# MainBoard_V1_3.net
KiCad netlist of a schematic drawn in EAGLE
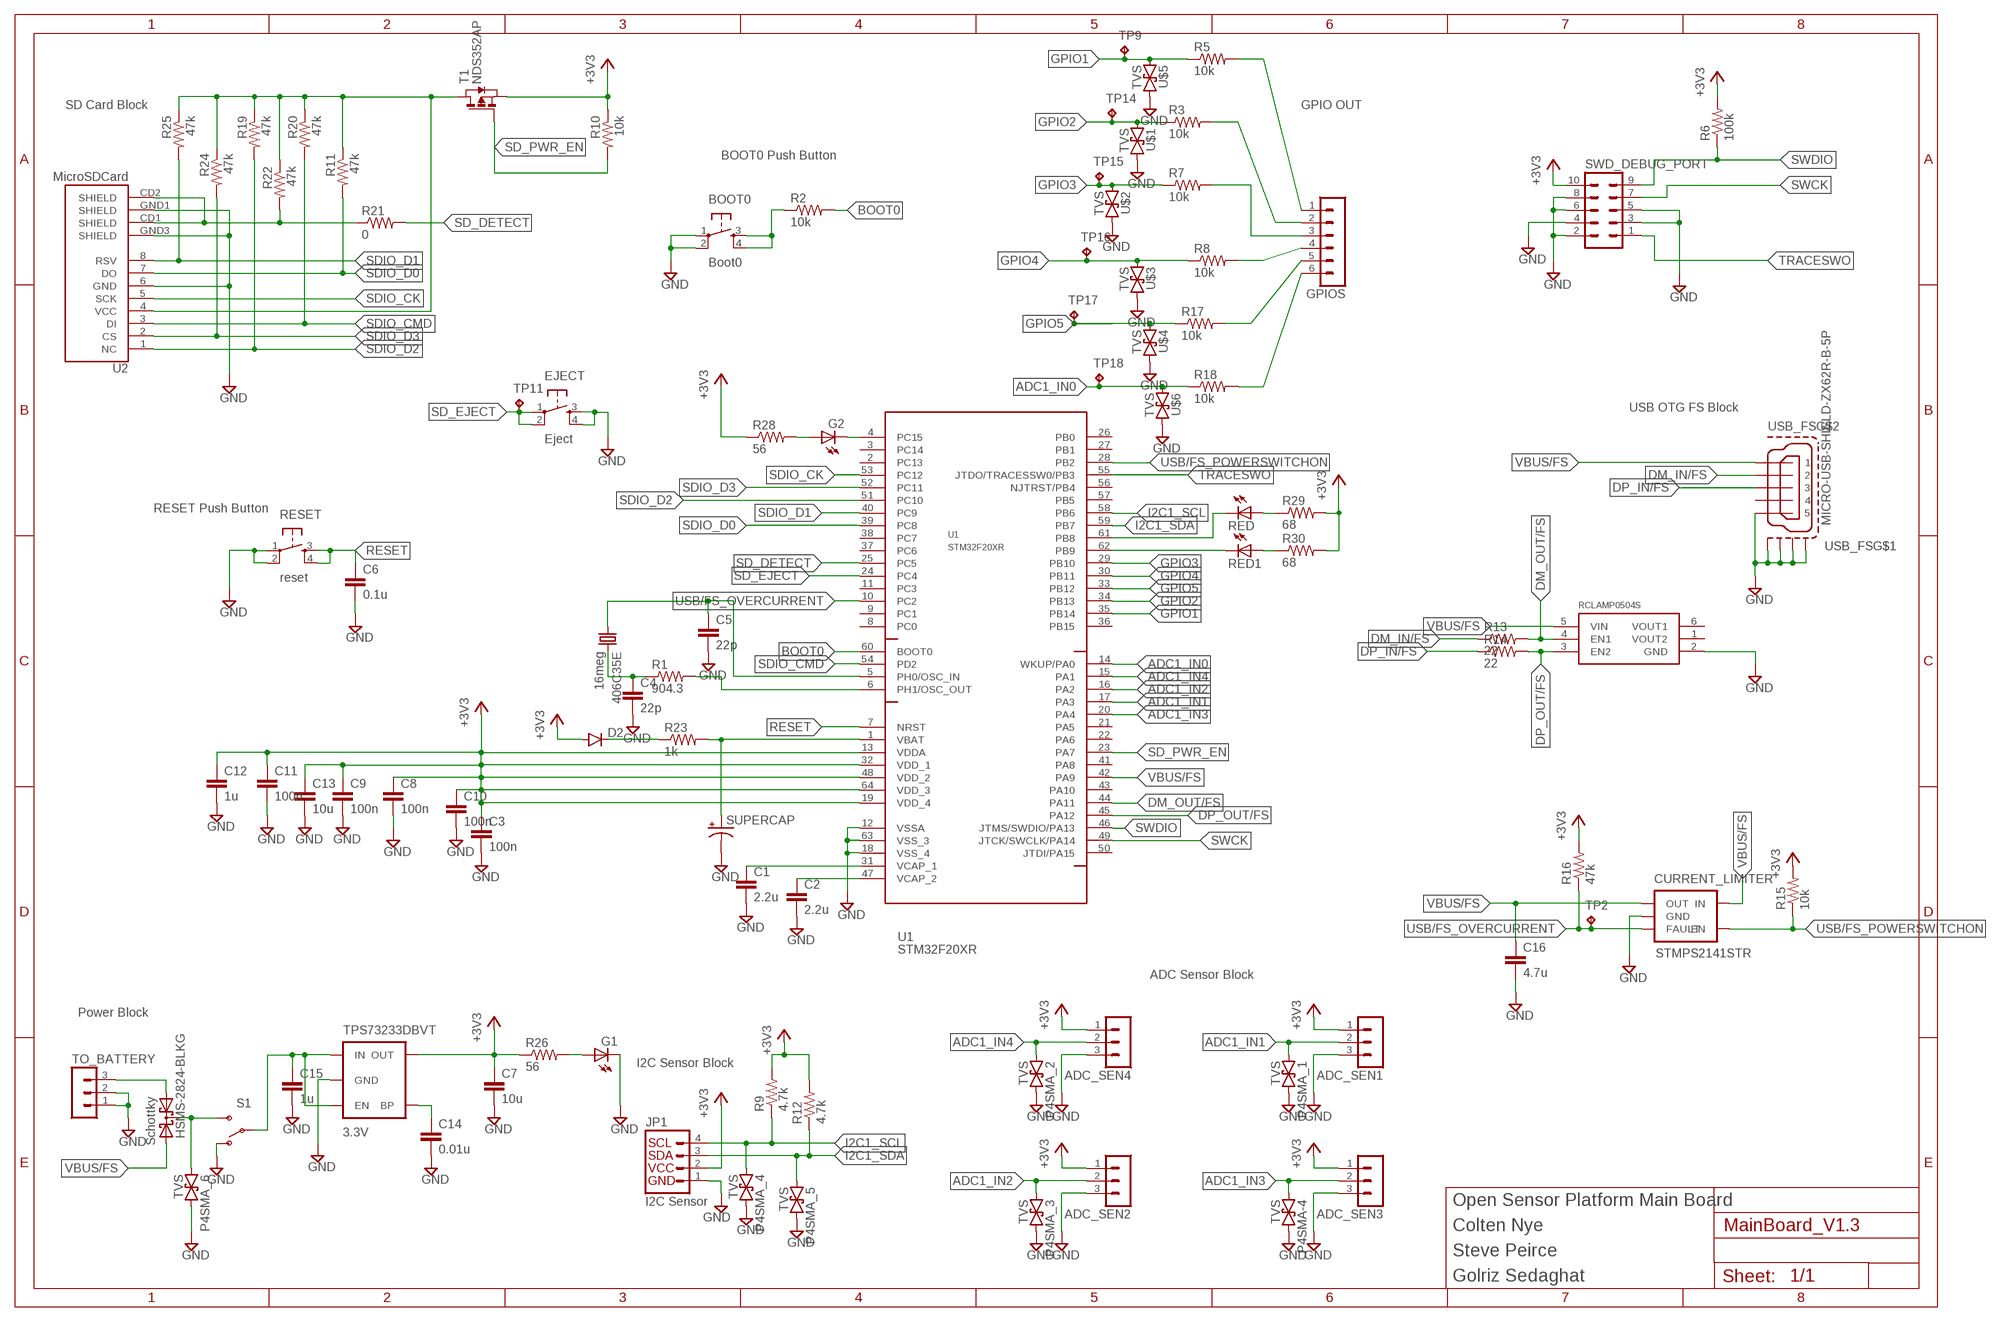
[diagram p0: schematic, sheet 1]

(export (version "E")
  (design (tool "Eeschema 10.0.6"))
  (components
    (comp (ref "406C35E")
      (value "16meg")
      (footprint "eagle-import:CTS406")
      (libsource (lib "eagle-import") (part "CRYSTALCTS406"))
    )
    (comp (ref "ADC_SEN1")
      (value "MA03-1")
      (footprint "eagle-import:MA03-1")
      (libsource (lib "eagle-import") (part "MA03-1"))
    )
    (comp (ref "ADC_SEN2")
      (value "MA03-1")
      (footprint "eagle-import:MA03-1")
      (libsource (lib "eagle-import") (part "MA03-1"))
    )
    (comp (ref "ADC_SEN3")
      (value "MA03-1")
      (footprint "eagle-import:MA03-1")
      (libsource (lib "eagle-import") (part "MA03-1"))
    )
    (comp (ref "ADC_SEN4")
      (value "MA03-1")
      (footprint "eagle-import:MA03-1")
      (libsource (lib "eagle-import") (part "MA03-1"))
    )
    (comp (ref "BOOT0")
      (value "Boot0")
      (footprint "eagle-import:TACTILE-SWITCH-SMD")
      (libsource (lib "eagle-import") (part "TAC_SWITCHSMD"))
    )
    (comp (ref "C1")
      (value "2.2u")
      (footprint "eagle-import:C0805")
      (libsource (lib "eagle-import") (part "C-EUC0805"))
    )
    (comp (ref "C2")
      (value "2.2u")
      (footprint "eagle-import:C0805")
      (libsource (lib "eagle-import") (part "C-EUC0805"))
    )
    (comp (ref "C3")
      (value "100n")
      (footprint "eagle-import:C0805")
      (libsource (lib "eagle-import") (part "C-EUC0805"))
    )
    (comp (ref "C4")
      (value "22p")
      (footprint "eagle-import:C0805")
      (libsource (lib "eagle-import") (part "C-EUC0805"))
    )
    (comp (ref "C5")
      (value "22p")
      (footprint "eagle-import:C0805")
      (libsource (lib "eagle-import") (part "C-EUC0805"))
    )
    (comp (ref "C6")
      (value "0.1u")
      (footprint "eagle-import:C0805")
      (libsource (lib "eagle-import") (part "C-EUC0805"))
    )
    (comp (ref "C7")
      (value "10u")
      (footprint "eagle-import:C0805")
      (libsource (lib "eagle-import") (part "C-EUC0805"))
    )
    (comp (ref "C8")
      (value "100n")
      (footprint "eagle-import:C0805")
      (libsource (lib "eagle-import") (part "C-EUC0805"))
    )
    (comp (ref "C9")
      (value "100n")
      (footprint "eagle-import:C0805")
      (libsource (lib "eagle-import") (part "C-EUC0805"))
    )
    (comp (ref "C10")
      (value "100n")
      (footprint "eagle-import:C0805")
      (libsource (lib "eagle-import") (part "C-EUC0805"))
    )
    (comp (ref "C11")
      (value "100n")
      (footprint "eagle-import:C0805")
      (libsource (lib "eagle-import") (part "C-EUC0805"))
    )
    (comp (ref "C12")
      (value "1u")
      (footprint "eagle-import:C0805")
      (libsource (lib "eagle-import") (part "C-EUC0805"))
    )
    (comp (ref "C13")
      (value "10u")
      (footprint "eagle-import:C0805")
      (libsource (lib "eagle-import") (part "C-EUC0805"))
    )
    (comp (ref "C14")
      (value "0.01u")
      (footprint "eagle-import:C0805")
      (libsource (lib "eagle-import") (part "C-EUC0805"))
    )
    (comp (ref "C15")
      (value "1u")
      (footprint "eagle-import:C0805")
      (libsource (lib "eagle-import") (part "C-EUC0805"))
    )
    (comp (ref "C16")
      (value "4.7u")
      (footprint "eagle-import:C0805")
      (libsource (lib "eagle-import") (part "C-EUC0805"))
    )
    (comp (ref "CURRENT_LIMITER")
      (value "STMPS2141STR")
      (footprint "eagle-import:SOT23-5")
      (libsource (lib "eagle-import") (part "V_REG_NCP1400SOT23-5"))
    )
    (comp (ref "D2")
      (value "DIODESMA")
      (footprint "eagle-import:SMA-DIODE")
      (libsource (lib "eagle-import") (part "DIODESMA"))
    )
    (comp (ref "EJECT")
      (value "Eject")
      (footprint "eagle-import:TACTILE-SWITCH-SMD")
      (libsource (lib "eagle-import") (part "TAC_SWITCHSMD"))
    )
    (comp (ref "G1")
      (value "LEDSML0805")
      (footprint "eagle-import:SML0805")
      (libsource (lib "eagle-import") (part "LEDSML0805"))
    )
    (comp (ref "G2")
      (value "LEDSML0805")
      (footprint "eagle-import:SML0805")
      (libsource (lib "eagle-import") (part "LEDSML0805"))
    )
    (comp (ref "GPIOS")
      (value "MA06-1")
      (footprint "eagle-import:MA06-1")
      (libsource (lib "eagle-import") (part "MA06-1"))
    )
    (comp (ref "HSMS-2824-BLKG")
      (value "Schottky")
      (footprint "eagle-import:SOT23")
      (libsource (lib "eagle-import") (part "BAS70-05"))
    )
    (comp (ref "JP1")
      (value "I2C Sensor")
      (footprint "eagle-import:1X04")
      (libsource (lib "eagle-import") (part "I2C_STANDARD"))
    )
    (comp (ref "P4SMA-4")
      (value "TVS")
      (footprint "eagle-import:SMA-DIODE")
      (libsource (lib "eagle-import") (part "TVS"))
    )
    (comp (ref "P4SMA_1")
      (value "TVS")
      (footprint "eagle-import:SMA-DIODE")
      (libsource (lib "eagle-import") (part "TVS"))
    )
    (comp (ref "P4SMA_2")
      (value "TVS")
      (footprint "eagle-import:SMA-DIODE")
      (libsource (lib "eagle-import") (part "TVS"))
    )
    (comp (ref "P4SMA_3")
      (value "TVS")
      (footprint "eagle-import:SMA-DIODE")
      (libsource (lib "eagle-import") (part "TVS"))
    )
    (comp (ref "P4SMA_4")
      (value "TVS")
      (footprint "eagle-import:SMA-DIODE")
      (libsource (lib "eagle-import") (part "TVS"))
    )
    (comp (ref "P4SMA_5")
      (value "TVS")
      (footprint "eagle-import:SMA-DIODE")
      (libsource (lib "eagle-import") (part "TVS"))
    )
    (comp (ref "P4SMA_6")
      (value "TVS")
      (footprint "eagle-import:SMA-DIODE")
      (libsource (lib "eagle-import") (part "TVS"))
    )
    (comp (ref "R1")
      (value "904.3")
      (footprint "eagle-import:R0805")
      (libsource (lib "eagle-import") (part "R-US_R0805"))
    )
    (comp (ref "R2")
      (value "10k")
      (footprint "eagle-import:R0805")
      (libsource (lib "eagle-import") (part "R-US_R0805"))
    )
    (comp (ref "R3")
      (value "10k")
      (footprint "eagle-import:R0805")
      (libsource (lib "eagle-import") (part "R-US_R0805"))
    )
    (comp (ref "R5")
      (value "10k")
      (footprint "eagle-import:R0805")
      (libsource (lib "eagle-import") (part "R-US_R0805"))
    )
    (comp (ref "R6")
      (value "100k")
      (footprint "eagle-import:R0805")
      (libsource (lib "eagle-import") (part "R-US_R0805"))
    )
    (comp (ref "R7")
      (value "10k")
      (footprint "eagle-import:R0805")
      (libsource (lib "eagle-import") (part "R-US_R0805"))
    )
    (comp (ref "R8")
      (value "10k")
      (footprint "eagle-import:R0805")
      (libsource (lib "eagle-import") (part "R-US_R0805"))
    )
    (comp (ref "R9")
      (value "4.7k")
      (footprint "eagle-import:R0805")
      (libsource (lib "eagle-import") (part "R-US_R0805"))
    )
    (comp (ref "R10")
      (value "10k")
      (footprint "eagle-import:R0805")
      (libsource (lib "eagle-import") (part "R-US_R0805"))
    )
    (comp (ref "R11")
      (value "47k")
      (footprint "eagle-import:R0805")
      (libsource (lib "eagle-import") (part "R-US_R0805"))
    )
    (comp (ref "R12")
      (value "4.7k")
      (footprint "eagle-import:R0805")
      (libsource (lib "eagle-import") (part "R-US_R0805"))
    )
    (comp (ref "R13")
      (value "22")
      (footprint "eagle-import:R0805")
      (libsource (lib "eagle-import") (part "R-US_R0805"))
    )
    (comp (ref "R14")
      (value "22")
      (footprint "eagle-import:R0805")
      (libsource (lib "eagle-import") (part "R-US_R0805"))
    )
    (comp (ref "R15")
      (value "10k")
      (footprint "eagle-import:R0805")
      (libsource (lib "eagle-import") (part "R-US_R0805"))
    )
    (comp (ref "R16")
      (value "47k")
      (footprint "eagle-import:R0805")
      (libsource (lib "eagle-import") (part "R-US_R0805"))
    )
    (comp (ref "R17")
      (value "10k")
      (footprint "eagle-import:R0805")
      (libsource (lib "eagle-import") (part "R-US_R0805"))
    )
    (comp (ref "R18")
      (value "10k")
      (footprint "eagle-import:R0805")
      (libsource (lib "eagle-import") (part "R-US_R0805"))
    )
    (comp (ref "R19")
      (value "47k")
      (footprint "eagle-import:R0805")
      (libsource (lib "eagle-import") (part "R-US_R0805"))
    )
    (comp (ref "R20")
      (value "47k")
      (footprint "eagle-import:R0805")
      (libsource (lib "eagle-import") (part "R-US_R0805"))
    )
    (comp (ref "R21")
      (value "0")
      (footprint "eagle-import:R0805")
      (libsource (lib "eagle-import") (part "R-US_R0805"))
    )
    (comp (ref "R22")
      (value "47k")
      (footprint "eagle-import:R0805")
      (libsource (lib "eagle-import") (part "R-US_R0805"))
    )
    (comp (ref "R23")
      (value "1k")
      (footprint "eagle-import:R0805")
      (libsource (lib "eagle-import") (part "R-US_R0805"))
    )
    (comp (ref "R24")
      (value "47k")
      (footprint "eagle-import:R0805")
      (libsource (lib "eagle-import") (part "R-US_R0805"))
    )
    (comp (ref "R25")
      (value "47k")
      (footprint "eagle-import:R0805")
      (libsource (lib "eagle-import") (part "R-US_R0805"))
    )
    (comp (ref "R26")
      (value "56")
      (footprint "eagle-import:R0805")
      (libsource (lib "eagle-import") (part "R-US_R0805"))
    )
    (comp (ref "R28")
      (value "56")
      (footprint "eagle-import:R0805")
      (libsource (lib "eagle-import") (part "R-US_R0805"))
    )
    (comp (ref "R29")
      (value "68")
      (footprint "eagle-import:R0805")
      (libsource (lib "eagle-import") (part "R-US_R0805"))
    )
    (comp (ref "R30")
      (value "68")
      (footprint "eagle-import:R0805")
      (libsource (lib "eagle-import") (part "R-US_R0805"))
    )
    (comp (ref "RCLAMP0504S")
      (value "VREG_SOT23-6_DUALAP7312")
      (footprint "eagle-import:SOT23-6")
      (libsource (lib "eagle-import") (part "VREG_SOT23-6_DUALAP7312"))
    )
    (comp (ref "RED")
      (value "LEDSML0805")
      (footprint "eagle-import:SML0805")
      (libsource (lib "eagle-import") (part "LEDSML0805"))
    )
    (comp (ref "RED1")
      (value "LEDSML0805")
      (footprint "eagle-import:SML0805")
      (libsource (lib "eagle-import") (part "LEDSML0805"))
    )
    (comp (ref "RESET")
      (value "reset")
      (footprint "eagle-import:TACTILE-SWITCH-SMD")
      (libsource (lib "eagle-import") (part "TAC_SWITCHSMD"))
    )
    (comp (ref "S1")
      (value "SWITCH-SPDTSMD")
      (footprint "eagle-import:AYZ0202")
      (libsource (lib "eagle-import") (part "SWITCH-SPDTSMD"))
    )
    (comp (ref "SUPERCAP")
      (value "SUPERCAP")
      (footprint "eagle-import:414-VA5R")
      (libsource (lib "eagle-import") (part "SUPERCAP"))
    )
    (comp (ref "SWD_DEBUG_PORT")
      (value "MA05-2")
      (footprint "eagle-import:MA05-2")
      (libsource (lib "eagle-import") (part "MA05-2"))
    )
    (comp (ref "T1")
      (value "NDS352AP")
      (footprint "eagle-import:SOT-23")
      (libsource (lib "eagle-import") (part "PMOSSOT23"))
    )
    (comp (ref "TO_BATTERY")
      (value "MA03-1")
      (footprint "eagle-import:MA03-1")
      (libsource (lib "eagle-import") (part "MA03-1"))
    )
    (comp (ref "TP2")
      (value "TPB1,27")
      (footprint "eagle-import:B1,27")
      (libsource (lib "eagle-import") (part "TPB1,27"))
    )
    (comp (ref "TP9")
      (value "TPB1,27")
      (footprint "eagle-import:B1,27")
      (libsource (lib "eagle-import") (part "TPB1,27"))
    )
    (comp (ref "TP11")
      (value "TPB1,27")
      (footprint "eagle-import:B1,27")
      (libsource (lib "eagle-import") (part "TPB1,27"))
    )
    (comp (ref "TP14")
      (value "TPB1,27")
      (footprint "eagle-import:B1,27")
      (libsource (lib "eagle-import") (part "TPB1,27"))
    )
    (comp (ref "TP15")
      (value "TPB1,27")
      (footprint "eagle-import:B1,27")
      (libsource (lib "eagle-import") (part "TPB1,27"))
    )
    (comp (ref "TP16")
      (value "TPB1,27")
      (footprint "eagle-import:B1,27")
      (libsource (lib "eagle-import") (part "TPB1,27"))
    )
    (comp (ref "TP17")
      (value "TPB1,27")
      (footprint "eagle-import:B1,27")
      (libsource (lib "eagle-import") (part "TPB1,27"))
    )
    (comp (ref "TP18")
      (value "TPB1,27")
      (footprint "eagle-import:B1,27")
      (libsource (lib "eagle-import") (part "TPB1,27"))
    )
    (comp (ref "TPS73233DBVT")
      (value "3.3V")
      (footprint "eagle-import:SOT23-5")
      (libsource (lib "eagle-import") (part "V_REG_MIC52053.3V"))
    )
    (comp (ref "U$1")
      (value "TVS")
      (footprint "eagle-import:SMA-DIODE")
      (libsource (lib "eagle-import") (part "TVS"))
    )
    (comp (ref "U$2")
      (value "TVS")
      (footprint "eagle-import:SMA-DIODE")
      (libsource (lib "eagle-import") (part "TVS"))
    )
    (comp (ref "U$3")
      (value "TVS")
      (footprint "eagle-import:SMA-DIODE")
      (libsource (lib "eagle-import") (part "TVS"))
    )
    (comp (ref "U$4")
      (value "TVS")
      (footprint "eagle-import:SMA-DIODE")
      (libsource (lib "eagle-import") (part "TVS"))
    )
    (comp (ref "U$5")
      (value "TVS")
      (footprint "eagle-import:SMA-DIODE")
      (libsource (lib "eagle-import") (part "TVS"))
    )
    (comp (ref "U$6")
      (value "TVS")
      (footprint "eagle-import:SMA-DIODE")
      (libsource (lib "eagle-import") (part "TVS"))
    )
    (comp (ref "U1")
      (value "STM32F20XR")
      (footprint "eagle-import:LQFP64")
      (libsource (lib "eagle-import") (part "STM32F20XR"))
    )
    (comp (ref "U2")
      (value "MicroSDCard")
      (footprint "eagle-import:MICRO-SD-SOCKET-PP")
      (libsource (lib "eagle-import") (part "USD-SOCKETNEW"))
    )
    (comp (ref "USB_FS")
      (value "MICRO-USB-SHIELD-ZX62R-B-5P")
      (footprint "eagle-import:ZX62R-B-5P")
      (libsource (lib "eagle-import") (part "MICRO-USB-SHIELD-ZX62R-B-5P"))
    )
  )
  (nets
    (net (code "1") (name "+3V3") (class "Default")
      (node (ref "ADC_SEN1") (pin "1") (pinfunction "1_1") (pintype "passive"))
      (node (ref "ADC_SEN2") (pin "1") (pinfunction "1_1") (pintype "passive"))
      (node (ref "ADC_SEN3") (pin "1") (pinfunction "1_1") (pintype "passive"))
      (node (ref "ADC_SEN4") (pin "1") (pinfunction "1_1") (pintype "passive"))
      (node (ref "C10") (pin "1") (pinfunction "1_1") (pintype "passive"))
      (node (ref "C11") (pin "1") (pinfunction "1_1") (pintype "passive"))
      (node (ref "C12") (pin "1") (pinfunction "1_1") (pintype "passive"))
      (node (ref "C13") (pin "1") (pinfunction "1_1") (pintype "passive"))
      (node (ref "C3") (pin "1") (pinfunction "1_1") (pintype "passive"))
      (node (ref "C7") (pin "1") (pinfunction "1_1") (pintype "passive"))
      (node (ref "C8") (pin "1") (pinfunction "1_1") (pintype "passive"))
      (node (ref "C9") (pin "1") (pinfunction "1_1") (pintype "passive"))
      (node (ref "D2") (pin "A") (pinfunction "A_A") (pintype "passive"))
      (node (ref "JP1") (pin "2") (pinfunction "2_2") (pintype "passive"))
      (node (ref "R10") (pin "1") (pinfunction "1_1") (pintype "passive"))
      (node (ref "R12") (pin "2") (pinfunction "2_2") (pintype "passive"))
      (node (ref "R15") (pin "2") (pinfunction "2_2") (pintype "passive"))
      (node (ref "R16") (pin "2") (pinfunction "2_2") (pintype "passive"))
      (node (ref "R26") (pin "1") (pinfunction "1_1") (pintype "passive"))
      (node (ref "R28") (pin "1") (pinfunction "1_1") (pintype "passive"))
      (node (ref "R29") (pin "2") (pinfunction "2_2") (pintype "passive"))
      (node (ref "R30") (pin "2") (pinfunction "2_2") (pintype "passive"))
      (node (ref "R6") (pin "2") (pinfunction "2_2") (pintype "passive"))
      (node (ref "R9") (pin "2") (pinfunction "2_2") (pintype "passive"))
      (node (ref "SWD_DEBUG_PORT") (pin "10") (pinfunction "10_10") (pintype "passive"))
      (node (ref "T1") (pin "2") (pinfunction "S_2") (pintype "passive"))
      (node (ref "TPS73233DBVT") (pin "5") (pinfunction "OUT_5") (pintype "passive"))
      (node (ref "U1") (pin "13") (pinfunction "VDDA_13") (pintype "power_in"))
      (node (ref "U1") (pin "19") (pinfunction "VDD_4_19") (pintype "power_in"))
      (node (ref "U1") (pin "32") (pinfunction "VDD_1_32") (pintype "power_in"))
      (node (ref "U1") (pin "48") (pinfunction "VDD_2_48") (pintype "power_in"))
      (node (ref "U1") (pin "64") (pinfunction "VDD_3_64") (pintype "power_in"))
    )
    (net (code "2") (name "ADC1_IN0") (class "Default")
      (node (ref "R18") (pin "1") (pinfunction "1_1") (pintype "passive"))
      (node (ref "TP18") (pin "TP") (pinfunction "TP_TP") (pintype "input"))
      (node (ref "U$6") (pin "A") (pinfunction "1_A") (pintype "passive"))
      (node (ref "U1") (pin "14") (pinfunction "WKUP/PA0_14") (pintype "bidirectional"))
    )
    (net (code "3") (name "ADC1_IN1") (class "Default")
      (node (ref "ADC_SEN1") (pin "2") (pinfunction "2_2") (pintype "passive"))
      (node (ref "P4SMA_1") (pin "A") (pinfunction "1_A") (pintype "passive"))
      (node (ref "U1") (pin "17") (pinfunction "PA3_17") (pintype "bidirectional"))
    )
    (net (code "4") (name "ADC1_IN2") (class "Default")
      (node (ref "ADC_SEN2") (pin "2") (pinfunction "2_2") (pintype "passive"))
      (node (ref "P4SMA_3") (pin "A") (pinfunction "1_A") (pintype "passive"))
      (node (ref "U1") (pin "16") (pinfunction "PA2_16") (pintype "bidirectional"))
    )
    (net (code "5") (name "ADC1_IN3") (class "Default")
      (node (ref "ADC_SEN3") (pin "2") (pinfunction "2_2") (pintype "passive"))
      (node (ref "P4SMA-4") (pin "A") (pinfunction "1_A") (pintype "passive"))
      (node (ref "U1") (pin "20") (pinfunction "PA4_20") (pintype "bidirectional"))
    )
    (net (code "6") (name "ADC1_IN4") (class "Default")
      (node (ref "ADC_SEN4") (pin "2") (pinfunction "2_2") (pintype "passive"))
      (node (ref "P4SMA_2") (pin "A") (pinfunction "1_A") (pintype "passive"))
      (node (ref "U1") (pin "15") (pinfunction "PA1_15") (pintype "bidirectional"))
    )
    (net (code "7") (name "BOOT0") (class "Default")
      (node (ref "R2") (pin "2") (pinfunction "2_2") (pintype "passive"))
      (node (ref "U1") (pin "60") (pinfunction "BOOT0_60") (pintype "bidirectional"))
    )
    (net (code "8") (name "DM_IN{slash}FS") (class "Default")
      (node (ref "R13") (pin "1") (pinfunction "1_1") (pintype "passive"))
      (node (ref "USB_FS") (pin "2") (pinfunction "2_2") (pintype "input"))
    )
    (net (code "9") (name "DM_OUT{slash}FS") (class "Default")
      (node (ref "R13") (pin "2") (pinfunction "2_2") (pintype "passive"))
      (node (ref "RCLAMP0504S") (pin "4") (pinfunction "EN1_4") (pintype "bidirectional"))
      (node (ref "U1") (pin "44") (pinfunction "PA11_44") (pintype "bidirectional"))
    )
    (net (code "10") (name "DP_IN{slash}FS") (class "Default")
      (node (ref "R14") (pin "1") (pinfunction "1_1") (pintype "passive"))
      (node (ref "USB_FS") (pin "3") (pinfunction "3_3") (pintype "input"))
    )
    (net (code "11") (name "DP_OUT{slash}FS") (class "Default")
      (node (ref "R14") (pin "2") (pinfunction "2_2") (pintype "passive"))
      (node (ref "RCLAMP0504S") (pin "3") (pinfunction "EN2_3") (pintype "bidirectional"))
      (node (ref "U1") (pin "45") (pinfunction "PA12_45") (pintype "bidirectional"))
    )
    (net (code "12") (name "GND") (class "Default")
      (node (ref "ADC_SEN1") (pin "3") (pinfunction "3_3") (pintype "passive"))
      (node (ref "ADC_SEN2") (pin "3") (pinfunction "3_3") (pintype "passive"))
      (node (ref "ADC_SEN3") (pin "3") (pinfunction "3_3") (pintype "passive"))
      (node (ref "ADC_SEN4") (pin "3") (pinfunction "3_3") (pintype "passive"))
      (node (ref "BOOT0") (pin "1") (pinfunction "1_1") (pintype "passive"))
      (node (ref "BOOT0") (pin "2") (pinfunction "2_2") (pintype "passive"))
      (node (ref "C1") (pin "2") (pinfunction "2_2") (pintype "passive"))
      (node (ref "C10") (pin "2") (pinfunction "2_2") (pintype "passive"))
      (node (ref "C11") (pin "2") (pinfunction "2_2") (pintype "passive"))
      (node (ref "C12") (pin "2") (pinfunction "2_2") (pintype "passive"))
      (node (ref "C13") (pin "2") (pinfunction "2_2") (pintype "passive"))
      (node (ref "C14") (pin "2") (pinfunction "2_2") (pintype "passive"))
      (node (ref "C15") (pin "2") (pinfunction "2_2") (pintype "passive"))
      (node (ref "C16") (pin "2") (pinfunction "2_2") (pintype "passive"))
      (node (ref "C2") (pin "2") (pinfunction "2_2") (pintype "passive"))
      (node (ref "C3") (pin "2") (pinfunction "2_2") (pintype "passive"))
      (node (ref "C4") (pin "2") (pinfunction "2_2") (pintype "passive"))
      (node (ref "C5") (pin "2") (pinfunction "2_2") (pintype "passive"))
      (node (ref "C6") (pin "2") (pinfunction "2_2") (pintype "passive"))
      (node (ref "C7") (pin "2") (pinfunction "2_2") (pintype "passive"))
      (node (ref "C8") (pin "2") (pinfunction "2_2") (pintype "passive"))
      (node (ref "C9") (pin "2") (pinfunction "2_2") (pintype "passive"))
      (node (ref "CURRENT_LIMITER") (pin "4") (pinfunction "GND_4") (pintype "input"))
      (node (ref "EJECT") (pin "3") (pinfunction "3_3") (pintype "passive"))
      (node (ref "EJECT") (pin "4") (pinfunction "4_4") (pintype "passive"))
      (node (ref "G1") (pin "C") (pinfunction "C_C") (pintype "passive"))
      (node (ref "JP1") (pin "1") (pinfunction "1_1") (pintype "passive"))
      (node (ref "P4SMA-4") (pin "C") (pinfunction "2_C") (pintype "passive"))
      (node (ref "P4SMA_1") (pin "C") (pinfunction "2_C") (pintype "passive"))
      (node (ref "P4SMA_2") (pin "C") (pinfunction "2_C") (pintype "passive"))
      (node (ref "P4SMA_3") (pin "C") (pinfunction "2_C") (pintype "passive"))
      (node (ref "P4SMA_4") (pin "C") (pinfunction "2_C") (pintype "passive"))
      (node (ref "P4SMA_5") (pin "C") (pinfunction "2_C") (pintype "passive"))
      (node (ref "P4SMA_6") (pin "C") (pinfunction "2_C") (pintype "passive"))
      (node (ref "RCLAMP0504S") (pin "2") (pinfunction "GND_2") (pintype "bidirectional"))
      (node (ref "RESET") (pin "1") (pinfunction "1_1") (pintype "passive"))
      (node (ref "RESET") (pin "2") (pinfunction "2_2") (pintype "passive"))
      (node (ref "S1") (pin "1") (pinfunction "O_1") (pintype "passive"))
      (node (ref "SUPERCAP") (pin "-") (pinfunction "-_-") (pintype "passive"))
      (node (ref "SWD_DEBUG_PORT") (pin "2") (pinfunction "2_2") (pintype "passive"))
      (node (ref "SWD_DEBUG_PORT") (pin "3") (pinfunction "3_3") (pintype "passive"))
      (node (ref "SWD_DEBUG_PORT") (pin "4") (pinfunction "4_4") (pintype "passive"))
      (node (ref "SWD_DEBUG_PORT") (pin "5") (pinfunction "5_5") (pintype "passive"))
      (node (ref "SWD_DEBUG_PORT") (pin "6") (pinfunction "6_6") (pintype "passive"))
      (node (ref "SWD_DEBUG_PORT") (pin "8") (pinfunction "8_8") (pintype "passive"))
      (node (ref "TO_BATTERY") (pin "1") (pinfunction "1_1") (pintype "passive"))
      (node (ref "TO_BATTERY") (pin "2") (pinfunction "2_2") (pintype "passive"))
      (node (ref "TPS73233DBVT") (pin "2") (pinfunction "GND_2") (pintype "input"))
      (node (ref "U$1") (pin "C") (pinfunction "2_C") (pintype "passive"))
      (node (ref "U$2") (pin "C") (pinfunction "2_C") (pintype "passive"))
      (node (ref "U$3") (pin "C") (pinfunction "2_C") (pintype "passive"))
      (node (ref "U$4") (pin "C") (pinfunction "2_C") (pintype "passive"))
      (node (ref "U$5") (pin "C") (pinfunction "2_C") (pintype "passive"))
      (node (ref "U$6") (pin "C") (pinfunction "2_C") (pintype "passive"))
      (node (ref "U1") (pin "12") (pinfunction "VSSA_12") (pintype "power_in"))
      (node (ref "U1") (pin "18") (pinfunction "VSS_4_18") (pintype "power_in"))
      (node (ref "U1") (pin "63") (pinfunction "VSS_3_63") (pintype "power_in"))
      (node (ref "U2") (pin "6") (pinfunction "GND_6") (pintype "bidirectional"))
      (node (ref "U2") (pin "GND1") (pinfunction "SHIELD_GND1") (pintype "bidirectional"))
      (node (ref "U2") (pin "GND3") (pinfunction "SHIELD_GND3") (pintype "bidirectional"))
      (node (ref "USB_FS") (pin "5") (pinfunction "5_5") (pintype "input"))
      (node (ref "USB_FS") (pin "M1") (pinfunction "S1_M1") (pintype "passive"))
      (node (ref "USB_FS") (pin "M2") (pinfunction "S2_M2") (pintype "passive"))
      (node (ref "USB_FS") (pin "M3") (pinfunction "S3_M3") (pintype "passive"))
      (node (ref "USB_FS") (pin "M4") (pinfunction "S4_M4") (pintype "passive"))
    )
    (net (code "13") (name "GPIO1") (class "Default")
      (node (ref "R5") (pin "1") (pinfunction "1_1") (pintype "passive"))
      (node (ref "TP9") (pin "TP") (pinfunction "TP_TP") (pintype "input"))
      (node (ref "U$5") (pin "A") (pinfunction "1_A") (pintype "passive"))
      (node (ref "U1") (pin "35") (pinfunction "PB14_35") (pintype "bidirectional"))
    )
    (net (code "14") (name "GPIO2") (class "Default")
      (node (ref "R3") (pin "1") (pinfunction "1_1") (pintype "passive"))
      (node (ref "TP14") (pin "TP") (pinfunction "TP_TP") (pintype "input"))
      (node (ref "U$1") (pin "A") (pinfunction "1_A") (pintype "passive"))
      (node (ref "U1") (pin "34") (pinfunction "PB13_34") (pintype "bidirectional"))
    )
    (net (code "15") (name "GPIO3") (class "Default")
      (node (ref "R7") (pin "1") (pinfunction "1_1") (pintype "passive"))
      (node (ref "TP15") (pin "TP") (pinfunction "TP_TP") (pintype "input"))
      (node (ref "U$2") (pin "A") (pinfunction "1_A") (pintype "passive"))
      (node (ref "U1") (pin "29") (pinfunction "PB10_29") (pintype "bidirectional"))
    )
    (net (code "16") (name "GPIO4") (class "Default")
      (node (ref "R8") (pin "1") (pinfunction "1_1") (pintype "passive"))
      (node (ref "TP16") (pin "TP") (pinfunction "TP_TP") (pintype "input"))
      (node (ref "U$3") (pin "A") (pinfunction "1_A") (pintype "passive"))
      (node (ref "U1") (pin "30") (pinfunction "PB11_30") (pintype "bidirectional"))
    )
    (net (code "17") (name "GPIO5") (class "Default")
      (node (ref "R17") (pin "1") (pinfunction "1_1") (pintype "passive"))
      (node (ref "TP17") (pin "TP") (pinfunction "TP_TP") (pintype "input"))
      (node (ref "U$4") (pin "A") (pinfunction "1_A") (pintype "passive"))
      (node (ref "U1") (pin "33") (pinfunction "PB12_33") (pintype "bidirectional"))
    )
    (net (code "18") (name "I2C1_SCL") (class "Default")
      (node (ref "JP1") (pin "4") (pinfunction "4_4") (pintype "passive"))
      (node (ref "P4SMA_4") (pin "A") (pinfunction "1_A") (pintype "passive"))
      (node (ref "R9") (pin "1") (pinfunction "1_1") (pintype "passive"))
      (node (ref "U1") (pin "58") (pinfunction "PB6_58") (pintype "bidirectional"))
    )
    (net (code "19") (name "I2C1_SDA") (class "Default")
      (node (ref "JP1") (pin "3") (pinfunction "3_3") (pintype "passive"))
      (node (ref "P4SMA_5") (pin "A") (pinfunction "1_A") (pintype "passive"))
      (node (ref "R12") (pin "1") (pinfunction "1_1") (pintype "passive"))
      (node (ref "U1") (pin "59") (pinfunction "PB7_59") (pintype "bidirectional"))
    )
    (net (code "20") (name "Net-(406C35E-2)") (class "Default")
      (node (ref "406C35E") (pin "3") (pinfunction "2_3") (pintype "passive"))
      (node (ref "C4") (pin "1") (pinfunction "1_1") (pintype "passive"))
      (node (ref "R1") (pin "1") (pinfunction "1_1") (pintype "passive"))
    )
    (net (code "21") (name "Net-(BOOT0-Pad3)") (class "Default")
      (node (ref "BOOT0") (pin "3") (pinfunction "3_3") (pintype "passive"))
      (node (ref "BOOT0") (pin "4") (pinfunction "4_4") (pintype "passive"))
      (node (ref "R2") (pin "1") (pinfunction "1_1") (pintype "passive"))
    )
    (net (code "22") (name "Net-(D2-PadC)") (class "Default")
      (node (ref "D2") (pin "C") (pinfunction "C_C") (pintype "passive"))
      (node (ref "R23") (pin "1") (pinfunction "1_1") (pintype "passive"))
    )
    (net (code "23") (name "Net-(G1-PadA)") (class "Default")
      (node (ref "G1") (pin "A") (pinfunction "A_A") (pintype "passive"))
      (node (ref "R26") (pin "2") (pinfunction "2_2") (pintype "passive"))
    )
    (net (code "24") (name "Net-(G2-PadA)") (class "Default")
      (node (ref "G2") (pin "A") (pinfunction "A_A") (pintype "passive"))
      (node (ref "R28") (pin "2") (pinfunction "2_2") (pintype "passive"))
    )
    (net (code "25") (name "Net-(GPIOS-Pad1)") (class "Default")
      (node (ref "GPIOS") (pin "1") (pinfunction "1_1") (pintype "passive"))
      (node (ref "R5") (pin "2") (pinfunction "2_2") (pintype "passive"))
    )
    (net (code "26") (name "Net-(GPIOS-Pad2)") (class "Default")
      (node (ref "GPIOS") (pin "2") (pinfunction "2_2") (pintype "passive"))
      (node (ref "R3") (pin "2") (pinfunction "2_2") (pintype "passive"))
    )
    (net (code "27") (name "Net-(GPIOS-Pad3)") (class "Default")
      (node (ref "GPIOS") (pin "3") (pinfunction "3_3") (pintype "passive"))
      (node (ref "R7") (pin "2") (pinfunction "2_2") (pintype "passive"))
    )
    (net (code "28") (name "Net-(GPIOS-Pad4)") (class "Default")
      (node (ref "GPIOS") (pin "4") (pinfunction "4_4") (pintype "passive"))
      (node (ref "R8") (pin "2") (pinfunction "2_2") (pintype "passive"))
    )
    (net (code "29") (name "Net-(GPIOS-Pad5)") (class "Default")
      (node (ref "GPIOS") (pin "5") (pinfunction "5_5") (pintype "passive"))
      (node (ref "R17") (pin "2") (pinfunction "2_2") (pintype "passive"))
    )
    (net (code "30") (name "Net-(GPIOS-Pad6)") (class "Default")
      (node (ref "GPIOS") (pin "6") (pinfunction "6_6") (pintype "passive"))
      (node (ref "R18") (pin "2") (pinfunction "2_2") (pintype "passive"))
    )
    (net (code "31") (name "Net-(HSMS-2824-BLKG-A1)") (class "Default")
      (node (ref "HSMS-2824-BLKG") (pin "1") (pinfunction "A1_1") (pintype "passive"))
      (node (ref "TO_BATTERY") (pin "3") (pinfunction "3_3") (pintype "passive"))
    )
    (net (code "32") (name "Net-(HSMS-2824-BLKG-C)") (class "Default")
      (node (ref "HSMS-2824-BLKG") (pin "3") (pinfunction "C_3") (pintype "passive"))
      (node (ref "P4SMA_6") (pin "A") (pinfunction "1_A") (pintype "passive"))
      (node (ref "S1") (pin "3") (pinfunction "S_3") (pintype "passive"))
    )
    (net (code "33") (name "Net-(R21-Pad1)") (class "Default")
      (node (ref "R21") (pin "1") (pinfunction "1_1") (pintype "passive"))
      (node (ref "R22") (pin "2") (pinfunction "2_2") (pintype "passive"))
      (node (ref "U2") (pin "CD1") (pinfunction "SHIELD_CD1") (pintype "bidirectional"))
      (node (ref "U2") (pin "CD2") (pinfunction "SHIELD_CD2") (pintype "bidirectional"))
    )
    (net (code "34") (name "Net-(R29-Pad1)") (class "Default")
      (node (ref "R29") (pin "1") (pinfunction "1_1") (pintype "passive"))
      (node (ref "RED") (pin "A") (pinfunction "A_A") (pintype "passive"))
    )
    (net (code "35") (name "Net-(R30-Pad1)") (class "Default")
      (node (ref "R30") (pin "1") (pinfunction "1_1") (pintype "passive"))
      (node (ref "RED1") (pin "A") (pinfunction "A_A") (pintype "passive"))
    )
    (net (code "36") (name "Net-(S1-P)") (class "Default")
      (node (ref "C15") (pin "1") (pinfunction "1_1") (pintype "passive"))
      (node (ref "S1") (pin "2") (pinfunction "P_2") (pintype "passive"))
      (node (ref "TPS73233DBVT") (pin "1") (pinfunction "IN_1") (pintype "input"))
      (node (ref "TPS73233DBVT") (pin "3") (pinfunction "EN_3") (pintype "input"))
    )
    (net (code "37") (name "Net-(T1-D)") (class "Default")
      (node (ref "R11") (pin "1") (pinfunction "1_1") (pintype "passive"))
      (node (ref "R19") (pin "1") (pinfunction "1_1") (pintype "passive"))
      (node (ref "R20") (pin "1") (pinfunction "1_1") (pintype "passive"))
      (node (ref "R22") (pin "1") (pinfunction "1_1") (pintype "passive"))
      (node (ref "R24") (pin "1") (pinfunction "1_1") (pintype "passive"))
      (node (ref "R25") (pin "1") (pinfunction "1_1") (pintype "passive"))
      (node (ref "T1") (pin "1") (pinfunction "D_1") (pintype "passive"))
      (node (ref "U2") (pin "4") (pinfunction "VCC_4") (pintype "bidirectional"))
    )
    (net (code "38") (name "Net-(TPS73233DBVT-BP)") (class "Default")
      (node (ref "C14") (pin "1") (pinfunction "1_1") (pintype "passive"))
      (node (ref "TPS73233DBVT") (pin "4") (pinfunction "BP_4") (pintype "input"))
    )
    (net (code "39") (name "Net-(U1-PB8)") (class "Default")
      (node (ref "RED") (pin "C") (pinfunction "C_C") (pintype "passive"))
      (node (ref "U1") (pin "61") (pinfunction "PB8_61") (pintype "bidirectional"))
    )
    (net (code "40") (name "Net-(U1-PB9)") (class "Default")
      (node (ref "RED1") (pin "C") (pinfunction "C_C") (pintype "passive"))
      (node (ref "U1") (pin "62") (pinfunction "PB9_62") (pintype "bidirectional"))
    )
    (net (code "41") (name "Net-(U1-PC15)") (class "Default")
      (node (ref "G2") (pin "C") (pinfunction "C_C") (pintype "passive"))
      (node (ref "U1") (pin "4") (pinfunction "PC15_4") (pintype "bidirectional"))
    )
    (net (code "42") (name "Net-(U1-PH0{slash}OSC_IN)") (class "Default")
      (node (ref "406C35E") (pin "1") (pinfunction "1_1") (pintype "passive"))
      (node (ref "C5") (pin "1") (pinfunction "1_1") (pintype "passive"))
      (node (ref "U1") (pin "5") (pinfunction "PH0/OSC_IN_5") (pintype "bidirectional"))
    )
    (net (code "43") (name "Net-(U1-PH1{slash}OSC_OUT)") (class "Default")
      (node (ref "R1") (pin "2") (pinfunction "2_2") (pintype "passive"))
      (node (ref "U1") (pin "6") (pinfunction "PH1/OSC_OUT_6") (pintype "bidirectional"))
    )
    (net (code "44") (name "Net-(U1-VBAT)") (class "Default")
      (node (ref "R23") (pin "2") (pinfunction "2_2") (pintype "passive"))
      (node (ref "SUPERCAP") (pin "+") (pinfunction "+_+") (pintype "passive"))
      (node (ref "U1") (pin "1") (pinfunction "VBAT_1") (pintype "power_in"))
    )
    (net (code "45") (name "Net-(U1-VCAP_1)") (class "Default")
      (node (ref "C1") (pin "1") (pinfunction "1_1") (pintype "passive"))
      (node (ref "U1") (pin "31") (pinfunction "VCAP_1_31") (pintype "power_in"))
    )
    (net (code "46") (name "Net-(U1-VCAP_2)") (class "Default")
      (node (ref "C2") (pin "1") (pinfunction "1_1") (pintype "passive"))
      (node (ref "U1") (pin "47") (pinfunction "VCAP_2_47") (pintype "power_in"))
    )
    (net (code "47") (name "RESET") (class "Default")
      (node (ref "C6") (pin "1") (pinfunction "1_1") (pintype "passive"))
      (node (ref "RESET") (pin "3") (pinfunction "3_3") (pintype "passive"))
      (node (ref "RESET") (pin "4") (pinfunction "4_4") (pintype "passive"))
      (node (ref "U1") (pin "7") (pinfunction "NRST_7") (pintype "power_in"))
    )
    (net (code "48") (name "SDIO_CK") (class "Default")
      (node (ref "U1") (pin "53") (pinfunction "PC12_53") (pintype "bidirectional"))
      (node (ref "U2") (pin "5") (pinfunction "SCK_5") (pintype "bidirectional"))
    )
    (net (code "49") (name "SDIO_CMD") (class "Default")
      (node (ref "R20") (pin "2") (pinfunction "2_2") (pintype "passive"))
      (node (ref "U1") (pin "54") (pinfunction "PD2_54") (pintype "bidirectional"))
      (node (ref "U2") (pin "3") (pinfunction "DI_3") (pintype "bidirectional"))
    )
    (net (code "50") (name "SDIO_D0") (class "Default")
      (node (ref "R11") (pin "2") (pinfunction "2_2") (pintype "passive"))
      (node (ref "U1") (pin "39") (pinfunction "PC8_39") (pintype "bidirectional"))
      (node (ref "U2") (pin "7") (pinfunction "DO_7") (pintype "bidirectional"))
    )
    (net (code "51") (name "SDIO_D1") (class "Default")
      (node (ref "R25") (pin "2") (pinfunction "2_2") (pintype "passive"))
      (node (ref "U1") (pin "40") (pinfunction "PC9_40") (pintype "bidirectional"))
      (node (ref "U2") (pin "8") (pinfunction "RSV_8") (pintype "bidirectional"))
    )
    (net (code "52") (name "SDIO_D2") (class "Default")
      (node (ref "R19") (pin "2") (pinfunction "2_2") (pintype "passive"))
      (node (ref "U1") (pin "51") (pinfunction "PC10_51") (pintype "bidirectional"))
      (node (ref "U2") (pin "1") (pinfunction "NC_1") (pintype "bidirectional"))
    )
    (net (code "53") (name "SDIO_D3") (class "Default")
      (node (ref "R24") (pin "2") (pinfunction "2_2") (pintype "passive"))
      (node (ref "U1") (pin "52") (pinfunction "PC11_52") (pintype "bidirectional"))
      (node (ref "U2") (pin "2") (pinfunction "CS_2") (pintype "bidirectional"))
    )
    (net (code "54") (name "SD_DETECT") (class "Default")
      (node (ref "R21") (pin "2") (pinfunction "2_2") (pintype "passive"))
      (node (ref "U1") (pin "25") (pinfunction "PC5_25") (pintype "bidirectional"))
    )
    (net (code "55") (name "SD_EJECT") (class "Default")
      (node (ref "EJECT") (pin "1") (pinfunction "1_1") (pintype "passive"))
      (node (ref "EJECT") (pin "2") (pinfunction "2_2") (pintype "passive"))
      (node (ref "TP11") (pin "TP") (pinfunction "TP_TP") (pintype "input"))
      (node (ref "U1") (pin "24") (pinfunction "PC4_24") (pintype "bidirectional"))
    )
    (net (code "56") (name "SD_PWR_EN") (class "Default")
      (node (ref "R10") (pin "2") (pinfunction "2_2") (pintype "passive"))
      (node (ref "T1") (pin "3") (pinfunction "G_3") (pintype "passive"))
      (node (ref "U1") (pin "23") (pinfunction "PA7_23") (pintype "bidirectional"))
    )
    (net (code "57") (name "SWCK") (class "Default")
      (node (ref "SWD_DEBUG_PORT") (pin "7") (pinfunction "7_7") (pintype "passive"))
      (node (ref "U1") (pin "49") (pinfunction "JTCK/SWCLK/PA14_49") (pintype "bidirectional"))
    )
    (net (code "58") (name "SWDIO") (class "Default")
      (node (ref "R6") (pin "1") (pinfunction "1_1") (pintype "passive"))
      (node (ref "SWD_DEBUG_PORT") (pin "9") (pinfunction "9_9") (pintype "passive"))
      (node (ref "U1") (pin "46") (pinfunction "JTMS/SWDIO/PA13_46") (pintype "bidirectional"))
    )
    (net (code "59") (name "TRACESWO") (class "Default")
      (node (ref "SWD_DEBUG_PORT") (pin "1") (pinfunction "1_1") (pintype "passive"))
      (node (ref "U1") (pin "55") (pinfunction "JTDO/TRACESSW0/PB3_55") (pintype "bidirectional"))
    )
    (net (code "60") (name "USB{slash}FS_OVERCURRENT") (class "Default")
      (node (ref "CURRENT_LIMITER") (pin "3") (pinfunction "FAULT_3") (pintype "input"))
      (node (ref "R16") (pin "1") (pinfunction "1_1") (pintype "passive"))
      (node (ref "TP2") (pin "TP") (pinfunction "TP_TP") (pintype "input"))
      (node (ref "U1") (pin "10") (pinfunction "PC2_10") (pintype "bidirectional"))
    )
    (net (code "61") (name "USB{slash}FS_POWERSWITCHON") (class "Default")
      (node (ref "CURRENT_LIMITER") (pin "1") (pinfunction "EN_1") (pintype "input"))
      (node (ref "R15") (pin "1") (pinfunction "1_1") (pintype "passive"))
      (node (ref "U1") (pin "28") (pinfunction "PB2_28") (pintype "bidirectional"))
    )
    (net (code "62") (name "VBUS{slash}FS") (class "Default")
      (node (ref "C16") (pin "1") (pinfunction "1_1") (pintype "passive"))
      (node (ref "CURRENT_LIMITER") (pin "2") (pinfunction "OUT_2") (pintype "passive"))
      (node (ref "CURRENT_LIMITER") (pin "5") (pinfunction "IN_5") (pintype "input"))
      (node (ref "HSMS-2824-BLKG") (pin "2") (pinfunction "A2_2") (pintype "passive"))
      (node (ref "RCLAMP0504S") (pin "5") (pinfunction "VIN_5") (pintype "bidirectional"))
      (node (ref "U1") (pin "42") (pinfunction "PA9_42") (pintype "bidirectional"))
      (node (ref "USB_FS") (pin "1") (pinfunction "1_1") (pintype "input"))
    )
    (net (code "63") (name "unconnected-(RCLAMP0504S-VOUT1-Pad6)") (class "Default")
      (node (ref "RCLAMP0504S") (pin "6") (pinfunction "VOUT1_6") (pintype "bidirectional"))
    )
    (net (code "64") (name "unconnected-(RCLAMP0504S-VOUT2-Pad1)") (class "Default")
      (node (ref "RCLAMP0504S") (pin "1") (pinfunction "VOUT2_1") (pintype "bidirectional"))
    )
    (net (code "65") (name "unconnected-(U1-JTDI{slash}PA15-Pad50)") (class "Default")
      (node (ref "U1") (pin "50") (pinfunction "JTDI/PA15_50") (pintype "bidirectional"))
    )
    (net (code "66") (name "unconnected-(U1-NJTRST{slash}PB4-Pad56)") (class "Default")
      (node (ref "U1") (pin "56") (pinfunction "NJTRST/PB4_56") (pintype "bidirectional"))
    )
    (net (code "67") (name "unconnected-(U1-PA5-Pad21)") (class "Default")
      (node (ref "U1") (pin "21") (pinfunction "PA5_21") (pintype "bidirectional"))
    )
    (net (code "68") (name "unconnected-(U1-PA6-Pad22)") (class "Default")
      (node (ref "U1") (pin "22") (pinfunction "PA6_22") (pintype "bidirectional"))
    )
    (net (code "69") (name "unconnected-(U1-PA8-Pad41)") (class "Default")
      (node (ref "U1") (pin "41") (pinfunction "PA8_41") (pintype "bidirectional"))
    )
    (net (code "70") (name "unconnected-(U1-PA10-Pad43)") (class "Default")
      (node (ref "U1") (pin "43") (pinfunction "PA10_43") (pintype "bidirectional"))
    )
    (net (code "71") (name "unconnected-(U1-PB0-Pad26)") (class "Default")
      (node (ref "U1") (pin "26") (pinfunction "PB0_26") (pintype "bidirectional"))
    )
    (net (code "72") (name "unconnected-(U1-PB1-Pad27)") (class "Default")
      (node (ref "U1") (pin "27") (pinfunction "PB1_27") (pintype "bidirectional"))
    )
    (net (code "73") (name "unconnected-(U1-PB5-Pad57)") (class "Default")
      (node (ref "U1") (pin "57") (pinfunction "PB5_57") (pintype "bidirectional"))
    )
    (net (code "74") (name "unconnected-(U1-PB15-Pad36)") (class "Default")
      (node (ref "U1") (pin "36") (pinfunction "PB15_36") (pintype "bidirectional"))
    )
    (net (code "75") (name "unconnected-(U1-PC0-Pad8)") (class "Default")
      (node (ref "U1") (pin "8") (pinfunction "PC0_8") (pintype "bidirectional"))
    )
    (net (code "76") (name "unconnected-(U1-PC1-Pad9)") (class "Default")
      (node (ref "U1") (pin "9") (pinfunction "PC1_9") (pintype "bidirectional"))
    )
    (net (code "77") (name "unconnected-(U1-PC3-Pad11)") (class "Default")
      (node (ref "U1") (pin "11") (pinfunction "PC3_11") (pintype "bidirectional"))
    )
    (net (code "78") (name "unconnected-(U1-PC6-Pad37)") (class "Default")
      (node (ref "U1") (pin "37") (pinfunction "PC6_37") (pintype "bidirectional"))
    )
    (net (code "79") (name "unconnected-(U1-PC7-Pad38)") (class "Default")
      (node (ref "U1") (pin "38") (pinfunction "PC7_38") (pintype "bidirectional"))
    )
    (net (code "80") (name "unconnected-(U1-PC13-Pad2)") (class "Default")
      (node (ref "U1") (pin "2") (pinfunction "PC13_2") (pintype "bidirectional"))
    )
    (net (code "81") (name "unconnected-(U1-PC14-Pad3)") (class "Default")
      (node (ref "U1") (pin "3") (pinfunction "PC14_3") (pintype "bidirectional"))
    )
    (net (code "82") (name "unconnected-(USB_FS-Pad4)") (class "Default")
      (node (ref "USB_FS") (pin "4") (pinfunction "4_4") (pintype "input"))
    )
  )
)
